# brain.net
KiCad netlist of a schematic drawn in EAGLE
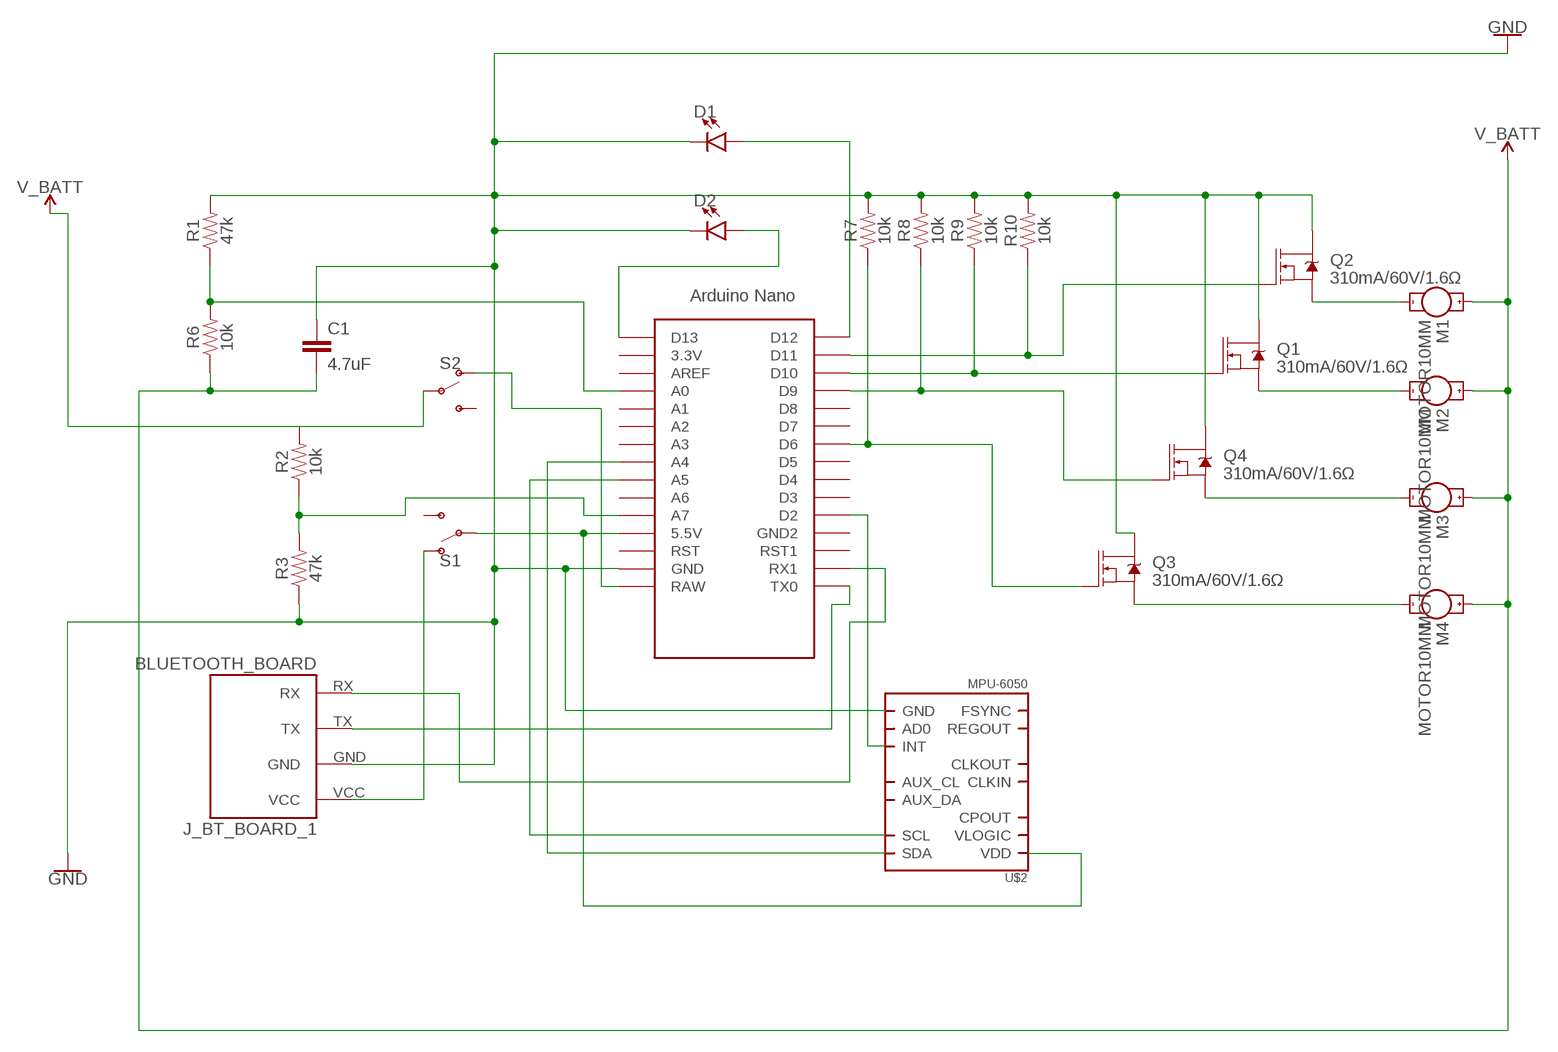
[diagram p0: schematic, sheet 1]

(export (version "E")
  (design (tool "Eeschema 10.0.6"))
  (components
    (comp (ref "C1")
      (value "4.7uF")
      (footprint "eagle-import:1206")
      (libsource (lib "eagle-import") (part "4.7UF-1206-16V-(+80/-20%)"))
    )
    (comp (ref "D1")
      (value "LED5MM")
      (footprint "eagle-import:LED_5MM")
      (libsource (lib "eagle-import") (part "LED5MM"))
    )
    (comp (ref "D2")
      (value "LED5MM")
      (footprint "eagle-import:LED_5MM")
      (libsource (lib "eagle-import") (part "LED5MM"))
    )
    (comp (ref "J_BT_BOARD_1")
      (value "BLUETOOTH_BOARD")
      (footprint "eagle-import:BT_BOARD_FOOTPRINT")
      (libsource (lib "eagle-import") (part "BLUETOOTH_BOARD"))
    )
    (comp (ref "M1")
      (value "MOTOR10MM")
      (footprint "eagle-import:VIBE-MOTOR-10MM")
      (libsource (lib "eagle-import") (part "MOTOR10MM"))
    )
    (comp (ref "M2")
      (value "MOTOR10MM")
      (footprint "eagle-import:VIBE-MOTOR-10MM")
      (libsource (lib "eagle-import") (part "MOTOR10MM"))
    )
    (comp (ref "M3")
      (value "MOTOR10MM")
      (footprint "eagle-import:VIBE-MOTOR-10MM")
      (libsource (lib "eagle-import") (part "MOTOR10MM"))
    )
    (comp (ref "M4")
      (value "MOTOR10MM")
      (footprint "eagle-import:VIBE-MOTOR-10MM")
      (libsource (lib "eagle-import") (part "MOTOR10MM"))
    )
    (comp (ref "Q1")
      (value "310mA/60V/1.6Ω")
      (footprint "eagle-import:SOT323")
      (libsource (lib "eagle-import") (part "MOSFET-NCH-2N7002PW"))
    )
    (comp (ref "Q2")
      (value "310mA/60V/1.6Ω")
      (footprint "eagle-import:SOT323")
      (libsource (lib "eagle-import") (part "MOSFET-NCH-2N7002PW"))
    )
    (comp (ref "Q3")
      (value "310mA/60V/1.6Ω")
      (footprint "eagle-import:SOT323")
      (libsource (lib "eagle-import") (part "MOSFET-NCH-2N7002PW"))
    )
    (comp (ref "Q4")
      (value "310mA/60V/1.6Ω")
      (footprint "eagle-import:SOT323")
      (libsource (lib "eagle-import") (part "MOSFET-NCH-2N7002PW"))
    )
    (comp (ref "R1")
      (value "47k")
      (footprint "eagle-import:0603")
      (libsource (lib "eagle-import") (part "47KOHM-0603-1/10W-1%"))
    )
    (comp (ref "R2")
      (value "10k")
      (footprint "eagle-import:AXIAL-0.3")
      (libsource (lib "eagle-import") (part "10KOHM-HORIZ-1/4W-1%"))
    )
    (comp (ref "R3")
      (value "47k")
      (footprint "eagle-import:0603")
      (libsource (lib "eagle-import") (part "47KOHM-0603-1/10W-1%"))
    )
    (comp (ref "R6")
      (value "10k")
      (footprint "eagle-import:AXIAL-0.3")
      (libsource (lib "eagle-import") (part "10KOHM-HORIZ-1/4W-1%"))
    )
    (comp (ref "R7")
      (value "10k")
      (footprint "eagle-import:AXIAL-0.3")
      (libsource (lib "eagle-import") (part "10KOHM-HORIZ-1/4W-1%"))
    )
    (comp (ref "R8")
      (value "10k")
      (footprint "eagle-import:AXIAL-0.3")
      (libsource (lib "eagle-import") (part "10KOHM-HORIZ-1/4W-1%"))
    )
    (comp (ref "R9")
      (value "10k")
      (footprint "eagle-import:AXIAL-0.3")
      (libsource (lib "eagle-import") (part "10KOHM-HORIZ-1/4W-1%"))
    )
    (comp (ref "R10")
      (value "10k")
      (footprint "eagle-import:AXIAL-0.3")
      (libsource (lib "eagle-import") (part "10KOHM-HORIZ-1/4W-1%"))
    )
    (comp (ref "S1")
      (value "SWITCH-SPDT-PTH-11.6X4.0MM")
      (footprint "eagle-import:SWITCH_SPDT_PTH_11.6X4.0MM")
      (libsource (lib "eagle-import") (part "SWITCH-SPDT-PTH-11.6X4.0MM"))
    )
    (comp (ref "S2")
      (value "SWITCH-SPDT-PTH-11.6X4.0MM")
      (footprint "eagle-import:SWITCH_SPDT_PTH_11.6X4.0MM")
      (libsource (lib "eagle-import") (part "SWITCH-SPDT-PTH-11.6X4.0MM"))
    )
    (comp (ref "U$1")
      (value "NANO")
      (footprint "eagle-import:NANO")
      (libsource (lib "eagle-import") (part "NANO"))
    )
    (comp (ref "U$2")
      (value "MPU-6050")
      (footprint "eagle-import:QFN.24.4X4")
      (libsource (lib "eagle-import") (part "MPU-6050"))
    )
  )
  (nets
    (net (code "1") (name "GND") (class "Default")
      (node (ref "C1") (pin "1") (pinfunction "1_1") (pintype "passive"))
      (node (ref "D1") (pin "K") (pinfunction "C_K") (pintype "passive"))
      (node (ref "D2") (pin "K") (pinfunction "C_K") (pintype "passive"))
      (node (ref "J_BT_BOARD_1") (pin "GND") (pinfunction "GND_GND") (pintype "bidirectional"))
      (node (ref "Q1") (pin "3") (pinfunction "D_3") (pintype "bidirectional"))
      (node (ref "Q2") (pin "3") (pinfunction "D_3") (pintype "bidirectional"))
      (node (ref "Q3") (pin "3") (pinfunction "D_3") (pintype "bidirectional"))
      (node (ref "Q4") (pin "3") (pinfunction "D_3") (pintype "bidirectional"))
      (node (ref "R1") (pin "2") (pinfunction "2_2") (pintype "passive"))
      (node (ref "R10") (pin "P$2") (pinfunction "2_P$2") (pintype "passive"))
      (node (ref "R3") (pin "1") (pinfunction "1_1") (pintype "passive"))
      (node (ref "R7") (pin "P$2") (pinfunction "2_P$2") (pintype "passive"))
      (node (ref "R8") (pin "P$2") (pinfunction "2_P$2") (pintype "passive"))
      (node (ref "R9") (pin "P$2") (pinfunction "2_P$2") (pintype "passive"))
      (node (ref "U$1") (pin "GND") (pinfunction "GND_GND") (pintype "bidirectional"))
      (node (ref "U$2") (pin "18") (pinfunction "GND_18") (pintype "bidirectional"))
    )
    (net (code "2") (name "Net-(D1-PadA)") (class "Default")
      (node (ref "D1") (pin "A") (pinfunction "A_A") (pintype "passive"))
      (node (ref "U$1") (pin "D12") (pinfunction "D12_D12") (pintype "bidirectional"))
    )
    (net (code "3") (name "Net-(D2-PadA)") (class "Default")
      (node (ref "D2") (pin "A") (pinfunction "A_A") (pintype "passive"))
      (node (ref "U$1") (pin "D13") (pinfunction "D13_D13") (pintype "bidirectional"))
    )
    (net (code "4") (name "Net-(J_BT_BOARD_1-PadRX)") (class "Default")
      (node (ref "J_BT_BOARD_1") (pin "RX") (pinfunction "RX_RX") (pintype "bidirectional"))
      (node (ref "U$1") (pin "RX1") (pinfunction "RX1_RX1") (pintype "bidirectional"))
    )
    (net (code "5") (name "Net-(J_BT_BOARD_1-PadTX)") (class "Default")
      (node (ref "J_BT_BOARD_1") (pin "TX") (pinfunction "TX_TX") (pintype "bidirectional"))
      (node (ref "U$1") (pin "TX0") (pinfunction "TX0_TX0") (pintype "bidirectional"))
    )
    (net (code "6") (name "Net-(Q1-G)") (class "Default")
      (node (ref "Q1") (pin "1") (pinfunction "G_1") (pintype "bidirectional"))
      (node (ref "R9") (pin "P$1") (pinfunction "1_P$1") (pintype "passive"))
      (node (ref "U$1") (pin "D10") (pinfunction "D10_D10") (pintype "bidirectional"))
    )
    (net (code "7") (name "Net-(Q1-S)") (class "Default")
      (node (ref "M2") (pin "-") (pinfunction "-_-") (pintype "bidirectional"))
      (node (ref "Q1") (pin "2") (pinfunction "S_2") (pintype "bidirectional"))
    )
    (net (code "8") (name "Net-(Q2-G)") (class "Default")
      (node (ref "Q2") (pin "1") (pinfunction "G_1") (pintype "bidirectional"))
      (node (ref "R10") (pin "P$1") (pinfunction "1_P$1") (pintype "passive"))
      (node (ref "U$1") (pin "D11") (pinfunction "D11_D11") (pintype "bidirectional"))
    )
    (net (code "9") (name "Net-(Q2-S)") (class "Default")
      (node (ref "M1") (pin "-") (pinfunction "-_-") (pintype "bidirectional"))
      (node (ref "Q2") (pin "2") (pinfunction "S_2") (pintype "bidirectional"))
    )
    (net (code "10") (name "Net-(Q3-G)") (class "Default")
      (node (ref "Q3") (pin "1") (pinfunction "G_1") (pintype "bidirectional"))
      (node (ref "R7") (pin "P$1") (pinfunction "1_P$1") (pintype "passive"))
      (node (ref "U$1") (pin "D6") (pinfunction "D6_D6") (pintype "bidirectional"))
    )
    (net (code "11") (name "Net-(Q3-S)") (class "Default")
      (node (ref "M4") (pin "-") (pinfunction "-_-") (pintype "bidirectional"))
      (node (ref "Q3") (pin "2") (pinfunction "S_2") (pintype "bidirectional"))
    )
    (net (code "12") (name "Net-(Q4-G)") (class "Default")
      (node (ref "Q4") (pin "1") (pinfunction "G_1") (pintype "bidirectional"))
      (node (ref "R8") (pin "P$1") (pinfunction "1_P$1") (pintype "passive"))
      (node (ref "U$1") (pin "D9") (pinfunction "D9_D9") (pintype "bidirectional"))
    )
    (net (code "13") (name "Net-(Q4-S)") (class "Default")
      (node (ref "M3") (pin "-") (pinfunction "-_-") (pintype "bidirectional"))
      (node (ref "Q4") (pin "2") (pinfunction "S_2") (pintype "bidirectional"))
    )
    (net (code "14") (name "Net-(R2-1)") (class "Default")
      (node (ref "R2") (pin "P$1") (pinfunction "1_P$1") (pintype "passive"))
      (node (ref "R3") (pin "2") (pinfunction "2_2") (pintype "passive"))
      (node (ref "U$1") (pin "A7") (pinfunction "A7_A7") (pintype "bidirectional"))
    )
    (net (code "15") (name "Net-(R6-2)") (class "Default")
      (node (ref "R1") (pin "1") (pinfunction "1_1") (pintype "passive"))
      (node (ref "R6") (pin "P$2") (pinfunction "2_P$2") (pintype "passive"))
      (node (ref "U$1") (pin "A0") (pinfunction "A0_A0") (pintype "bidirectional"))
    )
    (net (code "16") (name "Net-(S1-O)") (class "Default")
      (node (ref "J_BT_BOARD_1") (pin "VCC") (pinfunction "VCC_VCC") (pintype "bidirectional"))
      (node (ref "S1") (pin "1") (pinfunction "O_1") (pintype "passive"))
    )
    (net (code "17") (name "Net-(S1-P)") (class "Default")
      (node (ref "S1") (pin "2") (pinfunction "P_2") (pintype "passive"))
      (node (ref "U$1") (pin "5V") (pinfunction "5.5V_5V") (pintype "bidirectional"))
      (node (ref "U$2") (pin "13") (pinfunction "VDD_13") (pintype "bidirectional"))
    )
    (net (code "18") (name "Net-(S2-O)") (class "Default")
      (node (ref "S2") (pin "1") (pinfunction "O_1") (pintype "passive"))
      (node (ref "U$1") (pin "RAW") (pinfunction "RAW_RAW") (pintype "bidirectional"))
    )
    (net (code "19") (name "Net-(U$2-INT)") (class "Default")
      (node (ref "U$1") (pin "D2") (pinfunction "D2_D2") (pintype "bidirectional"))
      (node (ref "U$2") (pin "12") (pinfunction "INT_12") (pintype "bidirectional"))
    )
    (net (code "20") (name "Net-(U$2-SCL)") (class "Default")
      (node (ref "U$1") (pin "A5") (pinfunction "A5_A5") (pintype "bidirectional"))
      (node (ref "U$2") (pin "23") (pinfunction "SCL_23") (pintype "bidirectional"))
    )
    (net (code "21") (name "Net-(U$2-SDA)") (class "Default")
      (node (ref "U$1") (pin "A4") (pinfunction "A4_A4") (pintype "bidirectional"))
      (node (ref "U$2") (pin "24") (pinfunction "SDA_24") (pintype "bidirectional"))
    )
    (net (code "22") (name "V_BATT") (class "Default")
      (node (ref "C1") (pin "2") (pinfunction "2_2") (pintype "passive"))
      (node (ref "M1") (pin "+") (pinfunction "+_+") (pintype "bidirectional"))
      (node (ref "M2") (pin "+") (pinfunction "+_+") (pintype "bidirectional"))
      (node (ref "M3") (pin "+") (pinfunction "+_+") (pintype "bidirectional"))
      (node (ref "M4") (pin "+") (pinfunction "+_+") (pintype "bidirectional"))
      (node (ref "R6") (pin "P$1") (pinfunction "1_P$1") (pintype "passive"))
      (node (ref "S2") (pin "2") (pinfunction "P_2") (pintype "passive"))
    )
    (net (code "23") (name "unconnected-(R2-2-PadP$2)") (class "Default")
      (node (ref "R2") (pin "P$2") (pinfunction "2_P$2") (pintype "passive"))
    )
    (net (code "24") (name "unconnected-(S1-S-Pad3)") (class "Default")
      (node (ref "S1") (pin "3") (pinfunction "S_3") (pintype "passive"))
    )
    (net (code "25") (name "unconnected-(S2-S-Pad3)") (class "Default")
      (node (ref "S2") (pin "3") (pinfunction "S_3") (pintype "passive"))
    )
    (net (code "26") (name "unconnected-(U$1-GND2-PadGND1)") (class "Default")
      (node (ref "U$1") (pin "GND1") (pinfunction "GND2_GND1") (pintype "bidirectional"))
    )
    (net (code "27") (name "unconnected-(U$1-Pad3.3V)") (class "Default")
      (node (ref "U$1") (pin "3.3V") (pinfunction "3.3V_3.3V") (pintype "bidirectional"))
    )
    (net (code "28") (name "unconnected-(U$1-PadA1)") (class "Default")
      (node (ref "U$1") (pin "A1") (pinfunction "A1_A1") (pintype "bidirectional"))
    )
    (net (code "29") (name "unconnected-(U$1-PadA2)") (class "Default")
      (node (ref "U$1") (pin "A2") (pinfunction "A2_A2") (pintype "bidirectional"))
    )
    (net (code "30") (name "unconnected-(U$1-PadA3)") (class "Default")
      (node (ref "U$1") (pin "A3") (pinfunction "A3_A3") (pintype "bidirectional"))
    )
    (net (code "31") (name "unconnected-(U$1-PadA6)") (class "Default")
      (node (ref "U$1") (pin "A6") (pinfunction "A6_A6") (pintype "bidirectional"))
    )
    (net (code "32") (name "unconnected-(U$1-PadAREF)") (class "Default")
      (node (ref "U$1") (pin "AREF") (pinfunction "AREF_AREF") (pintype "bidirectional"))
    )
    (net (code "33") (name "unconnected-(U$1-PadD3)") (class "Default")
      (node (ref "U$1") (pin "D3") (pinfunction "D3_D3") (pintype "bidirectional"))
    )
    (net (code "34") (name "unconnected-(U$1-PadD4)") (class "Default")
      (node (ref "U$1") (pin "D4") (pinfunction "D4_D4") (pintype "bidirectional"))
    )
    (net (code "35") (name "unconnected-(U$1-PadD5)") (class "Default")
      (node (ref "U$1") (pin "D5") (pinfunction "D5_D5") (pintype "bidirectional"))
    )
    (net (code "36") (name "unconnected-(U$1-PadD7)") (class "Default")
      (node (ref "U$1") (pin "D7") (pinfunction "D7_D7") (pintype "bidirectional"))
    )
    (net (code "37") (name "unconnected-(U$1-PadD8)") (class "Default")
      (node (ref "U$1") (pin "D8") (pinfunction "D8_D8") (pintype "bidirectional"))
    )
    (net (code "38") (name "unconnected-(U$1-PadICSP1)") (class "Default")
      (node (ref "U$1") (pin "ICSP1") (pinfunction "ICSP1_ICSP1") (pintype "bidirectional"))
    )
    (net (code "39") (name "unconnected-(U$1-PadICSP2)") (class "Default")
      (node (ref "U$1") (pin "ICSP2") (pinfunction "ICSP2_ICSP2") (pintype "bidirectional"))
    )
    (net (code "40") (name "unconnected-(U$1-PadICSP3)") (class "Default")
      (node (ref "U$1") (pin "ICSP3") (pinfunction "ICSP3_ICSP3") (pintype "bidirectional"))
    )
    (net (code "41") (name "unconnected-(U$1-PadICSP4)") (class "Default")
      (node (ref "U$1") (pin "ICSP4") (pinfunction "ICSP4_ICSP4") (pintype "bidirectional"))
    )
    (net (code "42") (name "unconnected-(U$1-PadICSP5)") (class "Default")
      (node (ref "U$1") (pin "ICSP5") (pinfunction "ICSP5_ICSP5") (pintype "bidirectional"))
    )
    (net (code "43") (name "unconnected-(U$1-PadICSP6)") (class "Default")
      (node (ref "U$1") (pin "ICSP6") (pinfunction "ICSP6_ICSP6") (pintype "bidirectional"))
    )
    (net (code "44") (name "unconnected-(U$1-PadRST)") (class "Default")
      (node (ref "U$1") (pin "RST") (pinfunction "RST_RST") (pintype "bidirectional"))
    )
    (net (code "45") (name "unconnected-(U$1-PadRST1)") (class "Default")
      (node (ref "U$1") (pin "RST1") (pinfunction "RST1_RST1") (pintype "bidirectional"))
    )
    (net (code "46") (name "unconnected-(U$2-AD0-Pad9)") (class "Default")
      (node (ref "U$2") (pin "9") (pinfunction "AD0_9") (pintype "bidirectional"))
    )
    (net (code "47") (name "unconnected-(U$2-AUX_CL-Pad7)") (class "Default")
      (node (ref "U$2") (pin "7") (pinfunction "AUX_CL_7") (pintype "bidirectional"))
    )
    (net (code "48") (name "unconnected-(U$2-AUX_DA-Pad6)") (class "Default")
      (node (ref "U$2") (pin "6") (pinfunction "AUX_DA_6") (pintype "bidirectional"))
    )
    (net (code "49") (name "unconnected-(U$2-CLKIN-Pad1)") (class "Default")
      (node (ref "U$2") (pin "1") (pinfunction "CLKIN_1") (pintype "bidirectional"))
    )
    (net (code "50") (name "unconnected-(U$2-CLKOUT-Pad22)") (class "Default")
      (node (ref "U$2") (pin "22") (pinfunction "CLKOUT_22") (pintype "bidirectional"))
    )
    (net (code "51") (name "unconnected-(U$2-CPOUT-Pad20)") (class "Default")
      (node (ref "U$2") (pin "20") (pinfunction "CPOUT_20") (pintype "bidirectional"))
    )
    (net (code "52") (name "unconnected-(U$2-FSYNC-Pad11)") (class "Default")
      (node (ref "U$2") (pin "11") (pinfunction "FSYNC_11") (pintype "bidirectional"))
    )
    (net (code "53") (name "unconnected-(U$2-REGOUT-Pad10)") (class "Default")
      (node (ref "U$2") (pin "10") (pinfunction "REGOUT_10") (pintype "bidirectional"))
    )
    (net (code "54") (name "unconnected-(U$2-VLOGIC-Pad8)") (class "Default")
      (node (ref "U$2") (pin "8") (pinfunction "VLOGIC_8") (pintype "bidirectional"))
    )
  )
)
